# 02_IO_PORTS.net
KiCad netlist of a schematic drawn in Altium Designer
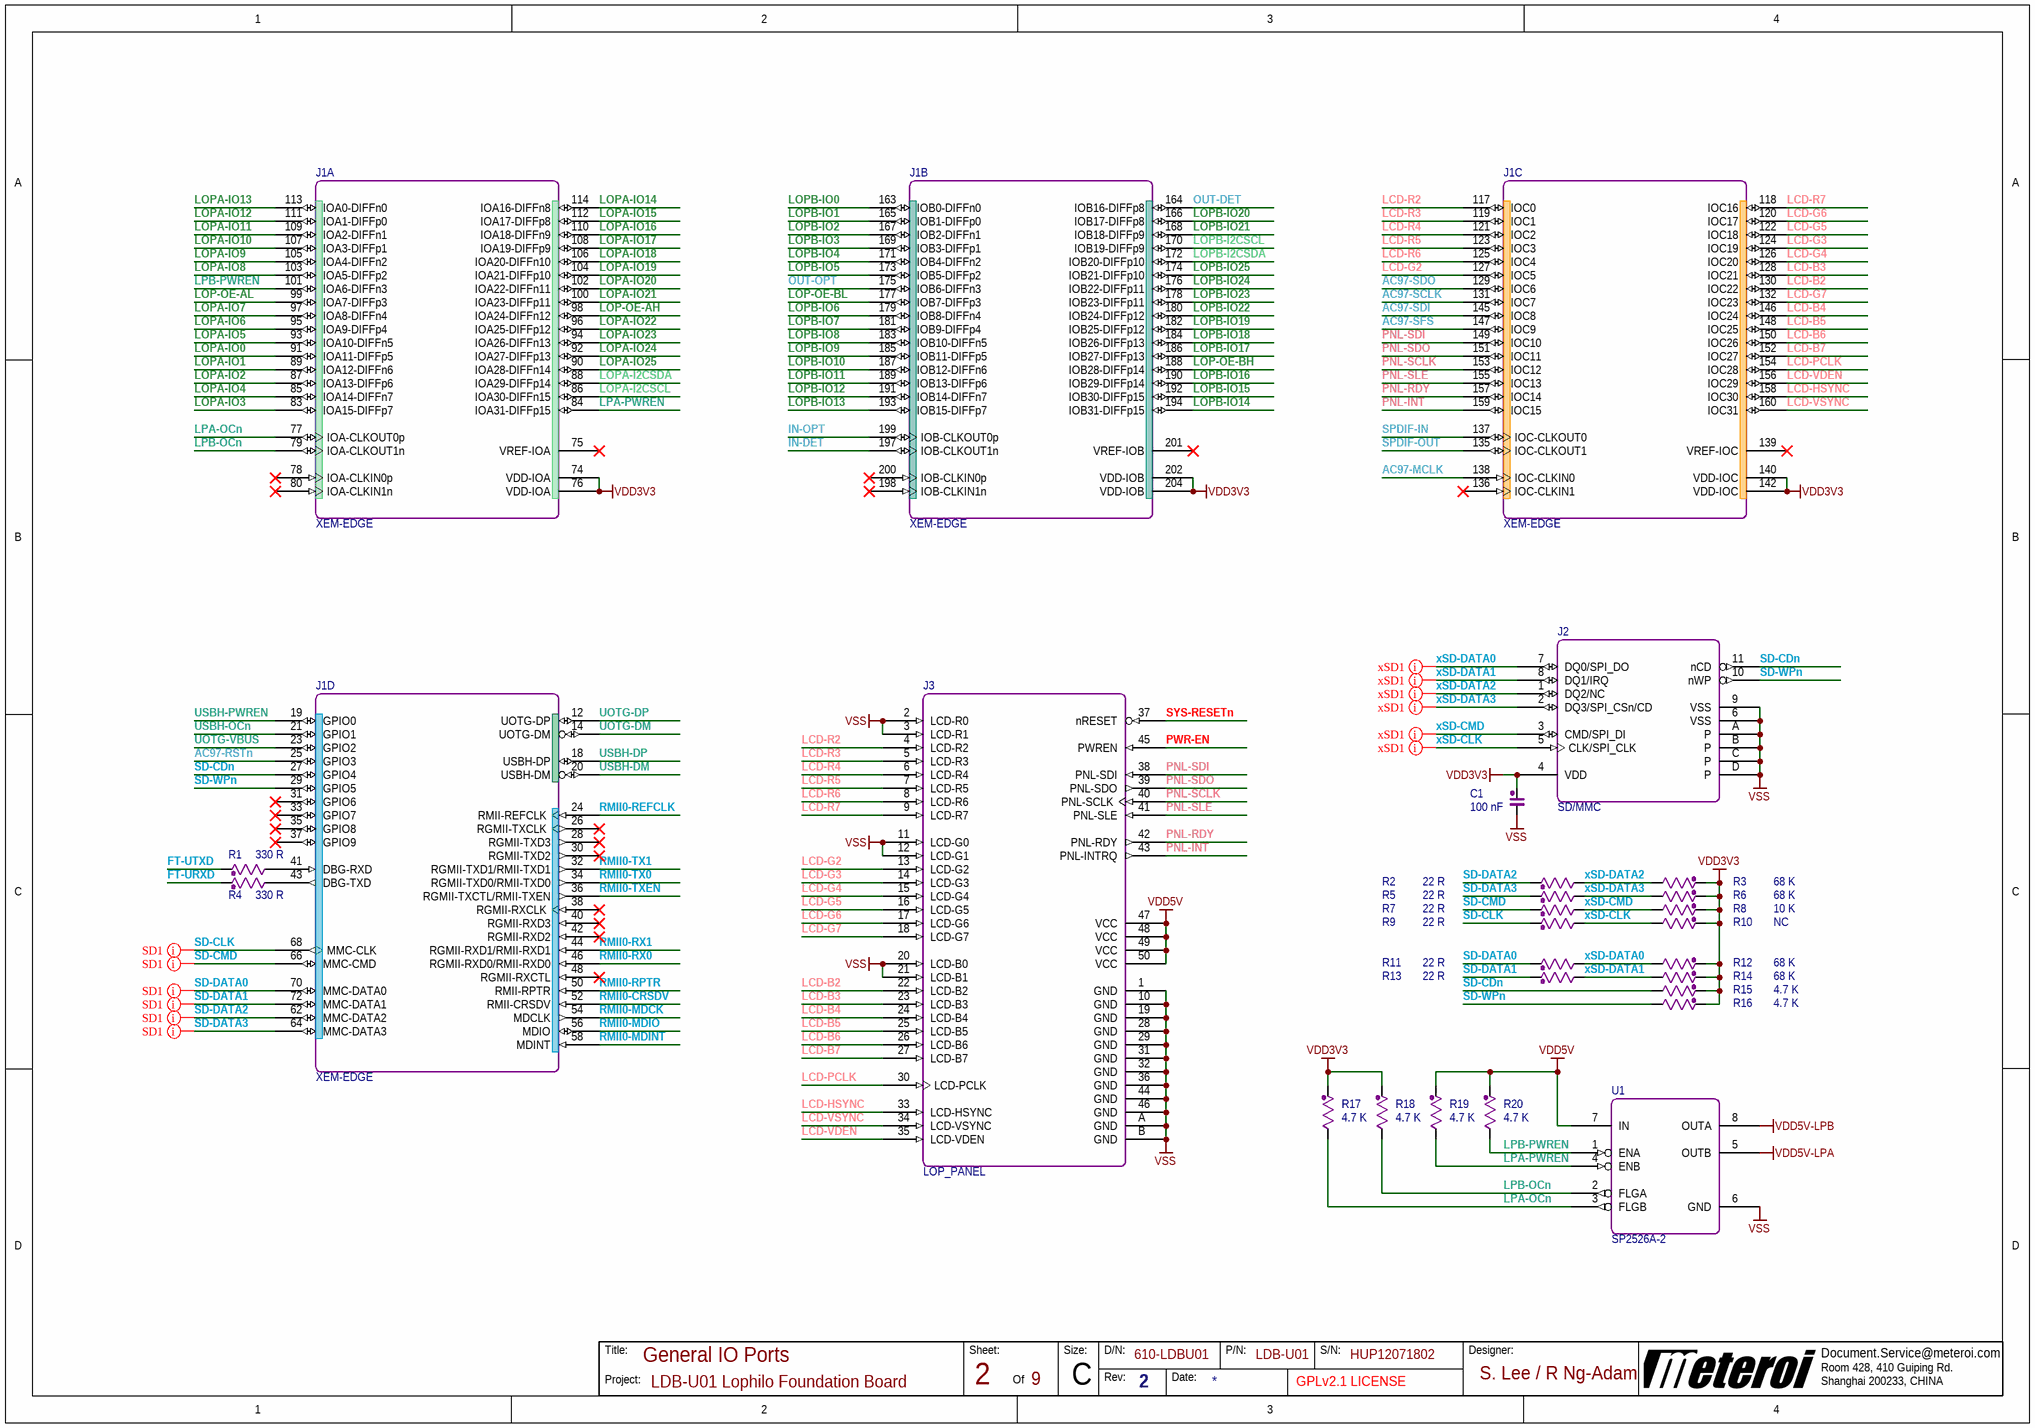
[diagram p0: 02_IO_PORTS.SchDoc]

(export (version "E")
  (design (tool "Eeschema 10.0.6"))
  (components
    (comp (ref "C1")
      (value "100 nF")
      (footprint "0603A1")
      (description "Normal Capacitor")
      (fields
        (field (name "PARTNUMBER") "0")
        (field (name "PUBLISHER") "Cowin")
        (field (name "DESIGNER") "shyul")
      )
      (libsource (lib "Basc_1_Passive") (part "CAP"))
    )
    (comp (ref "J1")
      (value "XEM-EDGE")
      (footprint "XEM-1S-204")
      (description "XEM Edge Connector 204-pins")
      (fields (field (name "PUBLISHER") "Cowin") (field (name "DESIGNER") "shyul"))
      (libsource (lib "PCB_LDB-U01") (part "XEM-SLOT"))
    )
    (comp (ref "J2")
      (value "SD/MMC")
      (footprint "SD_SOCKET_C")
      (description "SD/MMC CARD Socket")
      (fields
        (field (name "PARTNUMBER") "2041021-1")
        (field (name "PUBLISHER") "Cowin")
        (field (name "DESIGNER") "shyul")
      )
      (libsource (lib "Connector_1_General") (part "SD_JACK_2"))
    )
    (comp (ref "J3")
      (value "LOP_PANEL")
      (footprint "FPC_0P5_50A")
      (description "Lophilo Panel Interface")
      (fields (field (name "PUBLISHER") "Cowin") (field (name "DESIGNER") "shyul"))
      (libsource (lib "PCB_LDB-U01") (part "LOP_PANEL"))
    )
    (comp (ref "R1")
      (value "330 R")
      (footprint "0603A2")
      (description "Normal Resistor")
      (fields
        (field (name "PARTNUMBER") "0")
        (field (name "DESIGNER") "shyul")
        (field (name "PUBLISHER") "Cowin")
      )
      (libsource (lib "Basc_1_Passive") (part "RES"))
    )
    (comp (ref "R2")
      (value "22 R")
      (footprint "0402A2")
      (description "Normal Resistor")
      (fields
        (field (name "PARTNUMBER") "0")
        (field (name "DESIGNER") "shyul")
        (field (name "PUBLISHER") "Cowin")
      )
      (libsource (lib "Basc_1_Passive") (part "RES"))
    )
    (comp (ref "R3")
      (value "68 K")
      (footprint "0402A2")
      (description "Normal Resistor")
      (fields
        (field (name "PARTNUMBER") "0")
        (field (name "DESIGNER") "shyul")
        (field (name "PUBLISHER") "Cowin")
      )
      (libsource (lib "Basc_1_Passive") (part "RES"))
    )
    (comp (ref "R4")
      (value "330 R")
      (footprint "0603A2")
      (description "Normal Resistor")
      (fields
        (field (name "PARTNUMBER") "0")
        (field (name "DESIGNER") "shyul")
        (field (name "PUBLISHER") "Cowin")
      )
      (libsource (lib "Basc_1_Passive") (part "RES"))
    )
    (comp (ref "R5")
      (value "22 R")
      (footprint "0402A2")
      (description "Normal Resistor")
      (fields
        (field (name "PARTNUMBER") "0")
        (field (name "DESIGNER") "shyul")
        (field (name "PUBLISHER") "Cowin")
      )
      (libsource (lib "Basc_1_Passive") (part "RES"))
    )
    (comp (ref "R6")
      (value "68 K")
      (footprint "0402A2")
      (description "Normal Resistor")
      (fields
        (field (name "PARTNUMBER") "0")
        (field (name "DESIGNER") "shyul")
        (field (name "PUBLISHER") "Cowin")
      )
      (libsource (lib "Basc_1_Passive") (part "RES"))
    )
    (comp (ref "R7")
      (value "22 R")
      (footprint "0402A2")
      (description "Normal Resistor")
      (fields
        (field (name "PARTNUMBER") "0")
        (field (name "DESIGNER") "shyul")
        (field (name "PUBLISHER") "Cowin")
      )
      (libsource (lib "Basc_1_Passive") (part "RES"))
    )
    (comp (ref "R8")
      (value "10 K")
      (footprint "0402A2")
      (description "Normal Resistor")
      (fields
        (field (name "PARTNUMBER") "0")
        (field (name "DESIGNER") "shyul")
        (field (name "PUBLISHER") "Cowin")
      )
      (libsource (lib "Basc_1_Passive") (part "RES"))
    )
    (comp (ref "R9")
      (value "22 R")
      (footprint "0402A2")
      (description "Normal Resistor")
      (fields
        (field (name "PARTNUMBER") "0")
        (field (name "DESIGNER") "shyul")
        (field (name "PUBLISHER") "Cowin")
      )
      (libsource (lib "Basc_1_Passive") (part "RES"))
    )
    (comp (ref "R10")
      (value "NC")
      (footprint "0402A2")
      (description "Normal Resistor")
      (fields
        (field (name "PARTNUMBER") "0")
        (field (name "DESIGNER") "shyul")
        (field (name "PUBLISHER") "Cowin")
      )
      (libsource (lib "Basc_1_Passive") (part "RES"))
    )
    (comp (ref "R11")
      (value "22 R")
      (footprint "0402A2")
      (description "Normal Resistor")
      (fields
        (field (name "PARTNUMBER") "0")
        (field (name "DESIGNER") "shyul")
        (field (name "PUBLISHER") "Cowin")
      )
      (libsource (lib "Basc_1_Passive") (part "RES"))
    )
    (comp (ref "R12")
      (value "68 K")
      (footprint "0402A2")
      (description "Normal Resistor")
      (fields
        (field (name "PARTNUMBER") "0")
        (field (name "DESIGNER") "shyul")
        (field (name "PUBLISHER") "Cowin")
      )
      (libsource (lib "Basc_1_Passive") (part "RES"))
    )
    (comp (ref "R13")
      (value "22 R")
      (footprint "0402A2")
      (description "Normal Resistor")
      (fields
        (field (name "PARTNUMBER") "0")
        (field (name "DESIGNER") "shyul")
        (field (name "PUBLISHER") "Cowin")
      )
      (libsource (lib "Basc_1_Passive") (part "RES"))
    )
    (comp (ref "R14")
      (value "68 K")
      (footprint "0402A2")
      (description "Normal Resistor")
      (fields
        (field (name "PARTNUMBER") "0")
        (field (name "DESIGNER") "shyul")
        (field (name "PUBLISHER") "Cowin")
      )
      (libsource (lib "Basc_1_Passive") (part "RES"))
    )
    (comp (ref "R15")
      (value "4.7 K")
      (footprint "0603A2")
      (description "Normal Resistor")
      (fields
        (field (name "PARTNUMBER") "0")
        (field (name "DESIGNER") "shyul")
        (field (name "PUBLISHER") "Cowin")
      )
      (libsource (lib "Basc_1_Passive") (part "RES"))
    )
    (comp (ref "R16")
      (value "4.7 K")
      (footprint "0603A2")
      (description "Normal Resistor")
      (fields
        (field (name "PARTNUMBER") "0")
        (field (name "DESIGNER") "shyul")
        (field (name "PUBLISHER") "Cowin")
      )
      (libsource (lib "Basc_1_Passive") (part "RES"))
    )
    (comp (ref "R17")
      (value "4.7 K")
      (footprint "0402A2")
      (description "Normal Resistor")
      (fields
        (field (name "PARTNUMBER") "0")
        (field (name "DESIGNER") "shyul")
        (field (name "PUBLISHER") "Cowin")
      )
      (libsource (lib "Basc_1_Passive") (part "RES"))
    )
    (comp (ref "R18")
      (value "4.7 K")
      (footprint "0402A2")
      (description "Normal Resistor")
      (fields
        (field (name "PARTNUMBER") "0")
        (field (name "DESIGNER") "shyul")
        (field (name "PUBLISHER") "Cowin")
      )
      (libsource (lib "Basc_1_Passive") (part "RES"))
    )
    (comp (ref "R19")
      (value "4.7 K")
      (footprint "0603A2")
      (description "Normal Resistor")
      (fields
        (field (name "PARTNUMBER") "0")
        (field (name "DESIGNER") "shyul")
        (field (name "PUBLISHER") "Cowin")
      )
      (libsource (lib "Basc_1_Passive") (part "RES"))
    )
    (comp (ref "R20")
      (value "4.7 K")
      (footprint "0603A2")
      (description "Normal Resistor")
      (fields
        (field (name "PARTNUMBER") "0")
        (field (name "DESIGNER") "shyul")
        (field (name "PUBLISHER") "Cowin")
      )
      (libsource (lib "Basc_1_Passive") (part "RES"))
    )
    (comp (ref "U1")
      (value "SP2526A-2")
      (footprint "SOIC-8S")
      (description "Power Switch")
      (fields
        (field (name "PARTNUMBER") "SP2526A-2EN")
        (field (name "PUBLISHER") "Cowin")
        (field (name "DESIGNER") "shyul")
      )
      (libsource (lib "PCB_MDB-U01") (part "SP2526A-2"))
    )
  )
  (nets
    (net (code "1") (name "/AC97-MCLK") (class "Default")
      (node (ref "J1") (pin "138") (pinfunction "IOC-CLKIN0_138") (pintype "input"))
    )
    (net (code "2") (name "/AC97-RSTn") (class "Default")
      (node (ref "J1") (pin "25") (pinfunction "GPIO3_25") (pintype "bidirectional"))
    )
    (net (code "3") (name "/AC97-SCLK") (class "Default")
      (node (ref "J1") (pin "131") (pinfunction "IOC7_131") (pintype "bidirectional"))
    )
    (net (code "4") (name "/AC97-SDI") (class "Default")
      (node (ref "J1") (pin "145") (pinfunction "IOC8_145") (pintype "bidirectional"))
    )
    (net (code "5") (name "/AC97-SDO") (class "Default")
      (node (ref "J1") (pin "129") (pinfunction "IOC6_129") (pintype "bidirectional"))
    )
    (net (code "6") (name "/AC97-SFS") (class "Default")
      (node (ref "J1") (pin "147") (pinfunction "IOC9_147") (pintype "bidirectional"))
    )
    (net (code "7") (name "/FT-URXD") (class "Default")
      (node (ref "R4") (pin "2") (pinfunction "2_2") (pintype "passive"))
    )
    (net (code "8") (name "/FT-UTXD") (class "Default")
      (node (ref "R1") (pin "2") (pinfunction "2_2") (pintype "passive"))
    )
    (net (code "9") (name "/IN-DET") (class "Default")
      (node (ref "J1") (pin "197") (pinfunction "IOB-CLKOUT1n_197") (pintype "bidirectional"))
    )
    (net (code "10") (name "/IN-OPT") (class "Default")
      (node (ref "J1") (pin "199") (pinfunction "IOB-CLKOUT0p_199") (pintype "bidirectional"))
    )
    (net (code "11") (name "/LCD-B2") (class "Default")
      (node (ref "J1") (pin "130") (pinfunction "IOC22_130") (pintype "bidirectional"))
      (node (ref "J3") (pin "22") (pinfunction "LCD-B2_22") (pintype "input"))
    )
    (net (code "12") (name "/LCD-B3") (class "Default")
      (node (ref "J1") (pin "128") (pinfunction "IOC21_128") (pintype "bidirectional"))
      (node (ref "J3") (pin "23") (pinfunction "LCD-B3_23") (pintype "input"))
    )
    (net (code "13") (name "/LCD-B4") (class "Default")
      (node (ref "J1") (pin "146") (pinfunction "IOC24_146") (pintype "bidirectional"))
      (node (ref "J3") (pin "24") (pinfunction "LCD-B4_24") (pintype "input"))
    )
    (net (code "14") (name "/LCD-B5") (class "Default")
      (node (ref "J1") (pin "148") (pinfunction "IOC25_148") (pintype "bidirectional"))
      (node (ref "J3") (pin "25") (pinfunction "LCD-B5_25") (pintype "input"))
    )
    (net (code "15") (name "/LCD-B6") (class "Default")
      (node (ref "J1") (pin "150") (pinfunction "IOC26_150") (pintype "bidirectional"))
      (node (ref "J3") (pin "26") (pinfunction "LCD-B6_26") (pintype "input"))
    )
    (net (code "16") (name "/LCD-B7") (class "Default")
      (node (ref "J1") (pin "152") (pinfunction "IOC27_152") (pintype "bidirectional"))
      (node (ref "J3") (pin "27") (pinfunction "LCD-B7_27") (pintype "input"))
    )
    (net (code "17") (name "/LCD-G2") (class "Default")
      (node (ref "J1") (pin "127") (pinfunction "IOC5_127") (pintype "bidirectional"))
      (node (ref "J3") (pin "13") (pinfunction "LCD-G2_13") (pintype "input"))
    )
    (net (code "18") (name "/LCD-G3") (class "Default")
      (node (ref "J1") (pin "124") (pinfunction "IOC19_124") (pintype "bidirectional"))
      (node (ref "J3") (pin "14") (pinfunction "LCD-G3_14") (pintype "input"))
    )
    (net (code "19") (name "/LCD-G4") (class "Default")
      (node (ref "J1") (pin "126") (pinfunction "IOC20_126") (pintype "bidirectional"))
      (node (ref "J3") (pin "15") (pinfunction "LCD-G4_15") (pintype "input"))
    )
    (net (code "20") (name "/LCD-G5") (class "Default")
      (node (ref "J1") (pin "122") (pinfunction "IOC18_122") (pintype "bidirectional"))
      (node (ref "J3") (pin "16") (pinfunction "LCD-G5_16") (pintype "input"))
    )
    (net (code "21") (name "/LCD-G6") (class "Default")
      (node (ref "J1") (pin "120") (pinfunction "IOC17_120") (pintype "bidirectional"))
      (node (ref "J3") (pin "17") (pinfunction "LCD-G6_17") (pintype "input"))
    )
    (net (code "22") (name "/LCD-G7") (class "Default")
      (node (ref "J1") (pin "132") (pinfunction "IOC23_132") (pintype "bidirectional"))
      (node (ref "J3") (pin "18") (pinfunction "LCD-G7_18") (pintype "input"))
    )
    (net (code "23") (name "/LCD-HSYNC") (class "Default")
      (node (ref "J1") (pin "158") (pinfunction "IOC30_158") (pintype "bidirectional"))
      (node (ref "J3") (pin "33") (pinfunction "LCD-HSYNC_33") (pintype "input"))
    )
    (net (code "24") (name "/LCD-PCLK") (class "Default")
      (node (ref "J1") (pin "154") (pinfunction "IOC28_154") (pintype "bidirectional"))
      (node (ref "J3") (pin "30") (pinfunction "LCD-PCLK_30") (pintype "input"))
    )
    (net (code "25") (name "/LCD-R2") (class "Default")
      (node (ref "J1") (pin "117") (pinfunction "IOC0_117") (pintype "bidirectional"))
      (node (ref "J3") (pin "4") (pinfunction "LCD-R2_4") (pintype "input"))
    )
    (net (code "26") (name "/LCD-R3") (class "Default")
      (node (ref "J1") (pin "119") (pinfunction "IOC1_119") (pintype "bidirectional"))
      (node (ref "J3") (pin "5") (pinfunction "LCD-R3_5") (pintype "input"))
    )
    (net (code "27") (name "/LCD-R4") (class "Default")
      (node (ref "J1") (pin "121") (pinfunction "IOC2_121") (pintype "bidirectional"))
      (node (ref "J3") (pin "6") (pinfunction "LCD-R4_6") (pintype "input"))
    )
    (net (code "28") (name "/LCD-R5") (class "Default")
      (node (ref "J1") (pin "123") (pinfunction "IOC3_123") (pintype "bidirectional"))
      (node (ref "J3") (pin "7") (pinfunction "LCD-R5_7") (pintype "input"))
    )
    (net (code "29") (name "/LCD-R6") (class "Default")
      (node (ref "J1") (pin "125") (pinfunction "IOC4_125") (pintype "bidirectional"))
      (node (ref "J3") (pin "8") (pinfunction "LCD-R6_8") (pintype "input"))
    )
    (net (code "30") (name "/LCD-R7") (class "Default")
      (node (ref "J1") (pin "118") (pinfunction "IOC16_118") (pintype "bidirectional"))
      (node (ref "J3") (pin "9") (pinfunction "LCD-R7_9") (pintype "input"))
    )
    (net (code "31") (name "/LCD-VDEN") (class "Default")
      (node (ref "J1") (pin "156") (pinfunction "IOC29_156") (pintype "bidirectional"))
      (node (ref "J3") (pin "35") (pinfunction "LCD-VDEN_35") (pintype "input"))
    )
    (net (code "32") (name "/LCD-VSYNC") (class "Default")
      (node (ref "J1") (pin "160") (pinfunction "IOC31_160") (pintype "bidirectional"))
      (node (ref "J3") (pin "34") (pinfunction "LCD-VSYNC_34") (pintype "input"))
    )
    (net (code "33") (name "/LOP-OE-AH") (class "Default")
      (node (ref "J1") (pin "98") (pinfunction "IOA24-DIFFn12_98") (pintype "bidirectional"))
    )
    (net (code "34") (name "/LOP-OE-AL") (class "Default")
      (node (ref "J1") (pin "99") (pinfunction "IOA7-DIFFp3_99") (pintype "bidirectional"))
    )
    (net (code "35") (name "/LOP-OE-BH") (class "Default")
      (node (ref "J1") (pin "188") (pinfunction "IOB28-DIFFp14_188") (pintype "bidirectional"))
    )
    (net (code "36") (name "/LOP-OE-BL") (class "Default")
      (node (ref "J1") (pin "177") (pinfunction "IOB7-DIFFp3_177") (pintype "bidirectional"))
    )
    (net (code "37") (name "/LOPA-I2CSCL") (class "Default")
      (node (ref "J1") (pin "86") (pinfunction "IOA30-DIFFn15_86") (pintype "bidirectional"))
    )
    (net (code "38") (name "/LOPA-I2CSDA") (class "Default")
      (node (ref "J1") (pin "88") (pinfunction "IOA29-DIFFp14_88") (pintype "bidirectional"))
    )
    (net (code "39") (name "/LOPA-IO0") (class "Default")
      (node (ref "J1") (pin "91") (pinfunction "IOA11-DIFFp5_91") (pintype "bidirectional"))
    )
    (net (code "40") (name "/LOPA-IO1") (class "Default")
      (node (ref "J1") (pin "89") (pinfunction "IOA12-DIFFn6_89") (pintype "bidirectional"))
    )
    (net (code "41") (name "/LOPA-IO2") (class "Default")
      (node (ref "J1") (pin "87") (pinfunction "IOA13-DIFFp6_87") (pintype "bidirectional"))
    )
    (net (code "42") (name "/LOPA-IO3") (class "Default")
      (node (ref "J1") (pin "83") (pinfunction "IOA15-DIFFp7_83") (pintype "bidirectional"))
    )
    (net (code "43") (name "/LOPA-IO4") (class "Default")
      (node (ref "J1") (pin "85") (pinfunction "IOA14-DIFFn7_85") (pintype "bidirectional"))
    )
    (net (code "44") (name "/LOPA-IO5") (class "Default")
      (node (ref "J1") (pin "93") (pinfunction "IOA10-DIFFn5_93") (pintype "bidirectional"))
    )
    (net (code "45") (name "/LOPA-IO6") (class "Default")
      (node (ref "J1") (pin "95") (pinfunction "IOA9-DIFFp4_95") (pintype "bidirectional"))
    )
    (net (code "46") (name "/LOPA-IO7") (class "Default")
      (node (ref "J1") (pin "97") (pinfunction "IOA8-DIFFn4_97") (pintype "bidirectional"))
    )
    (net (code "47") (name "/LOPA-IO8") (class "Default")
      (node (ref "J1") (pin "103") (pinfunction "IOA5-DIFFp2_103") (pintype "bidirectional"))
    )
    (net (code "48") (name "/LOPA-IO9") (class "Default")
      (node (ref "J1") (pin "105") (pinfunction "IOA4-DIFFn2_105") (pintype "bidirectional"))
    )
    (net (code "49") (name "/LOPA-IO10") (class "Default")
      (node (ref "J1") (pin "107") (pinfunction "IOA3-DIFFp1_107") (pintype "bidirectional"))
    )
    (net (code "50") (name "/LOPA-IO11") (class "Default")
      (node (ref "J1") (pin "109") (pinfunction "IOA2-DIFFn1_109") (pintype "bidirectional"))
    )
    (net (code "51") (name "/LOPA-IO12") (class "Default")
      (node (ref "J1") (pin "111") (pinfunction "IOA1-DIFFp0_111") (pintype "bidirectional"))
    )
    (net (code "52") (name "/LOPA-IO13") (class "Default")
      (node (ref "J1") (pin "113") (pinfunction "IOA0-DIFFn0_113") (pintype "bidirectional"))
    )
    (net (code "53") (name "/LOPA-IO14") (class "Default")
      (node (ref "J1") (pin "114") (pinfunction "IOA16-DIFFn8_114") (pintype "bidirectional"))
    )
    (net (code "54") (name "/LOPA-IO15") (class "Default")
      (node (ref "J1") (pin "112") (pinfunction "IOA17-DIFFp8_112") (pintype "bidirectional"))
    )
    (net (code "55") (name "/LOPA-IO16") (class "Default")
      (node (ref "J1") (pin "110") (pinfunction "IOA18-DIFFn9_110") (pintype "bidirectional"))
    )
    (net (code "56") (name "/LOPA-IO17") (class "Default")
      (node (ref "J1") (pin "108") (pinfunction "IOA19-DIFFp9_108") (pintype "bidirectional"))
    )
    (net (code "57") (name "/LOPA-IO18") (class "Default")
      (node (ref "J1") (pin "106") (pinfunction "IOA20-DIFFn10_106") (pintype "bidirectional"))
    )
    (net (code "58") (name "/LOPA-IO19") (class "Default")
      (node (ref "J1") (pin "104") (pinfunction "IOA21-DIFFp10_104") (pintype "bidirectional"))
    )
    (net (code "59") (name "/LOPA-IO20") (class "Default")
      (node (ref "J1") (pin "102") (pinfunction "IOA22-DIFFn11_102") (pintype "bidirectional"))
    )
    (net (code "60") (name "/LOPA-IO21") (class "Default")
      (node (ref "J1") (pin "100") (pinfunction "IOA23-DIFFp11_100") (pintype "bidirectional"))
    )
    (net (code "61") (name "/LOPA-IO22") (class "Default")
      (node (ref "J1") (pin "96") (pinfunction "IOA25-DIFFp12_96") (pintype "bidirectional"))
    )
    (net (code "62") (name "/LOPA-IO23") (class "Default")
      (node (ref "J1") (pin "94") (pinfunction "IOA26-DIFFn13_94") (pintype "bidirectional"))
    )
    (net (code "63") (name "/LOPA-IO24") (class "Default")
      (node (ref "J1") (pin "92") (pinfunction "IOA27-DIFFp13_92") (pintype "bidirectional"))
    )
    (net (code "64") (name "/LOPA-IO25") (class "Default")
      (node (ref "J1") (pin "90") (pinfunction "IOA28-DIFFn14_90") (pintype "bidirectional"))
    )
    (net (code "65") (name "/LOPB-I2CSCL") (class "Default")
      (node (ref "J1") (pin "170") (pinfunction "IOB19-DIFFp9_170") (pintype "bidirectional"))
    )
    (net (code "66") (name "/LOPB-I2CSDA") (class "Default")
      (node (ref "J1") (pin "172") (pinfunction "IOB20-DIFFp10_172") (pintype "bidirectional"))
    )
    (net (code "67") (name "/LOPB-IO0") (class "Default")
      (node (ref "J1") (pin "163") (pinfunction "IOB0-DIFFn0_163") (pintype "bidirectional"))
    )
    (net (code "68") (name "/LOPB-IO1") (class "Default")
      (node (ref "J1") (pin "165") (pinfunction "IOB1-DIFFp0_165") (pintype "bidirectional"))
    )
    (net (code "69") (name "/LOPB-IO2") (class "Default")
      (node (ref "J1") (pin "167") (pinfunction "IOB2-DIFFn1_167") (pintype "bidirectional"))
    )
    (net (code "70") (name "/LOPB-IO3") (class "Default")
      (node (ref "J1") (pin "169") (pinfunction "IOB3-DIFFp1_169") (pintype "bidirectional"))
    )
    (net (code "71") (name "/LOPB-IO4") (class "Default")
      (node (ref "J1") (pin "171") (pinfunction "IOB4-DIFFn2_171") (pintype "bidirectional"))
    )
    (net (code "72") (name "/LOPB-IO5") (class "Default")
      (node (ref "J1") (pin "173") (pinfunction "IOB5-DIFFp2_173") (pintype "bidirectional"))
    )
    (net (code "73") (name "/LOPB-IO6") (class "Default")
      (node (ref "J1") (pin "179") (pinfunction "IOB8-DIFFn4_179") (pintype "bidirectional"))
    )
    (net (code "74") (name "/LOPB-IO7") (class "Default")
      (node (ref "J1") (pin "181") (pinfunction "IOB9-DIFFp4_181") (pintype "bidirectional"))
    )
    (net (code "75") (name "/LOPB-IO8") (class "Default")
      (node (ref "J1") (pin "183") (pinfunction "IOB10-DIFFn5_183") (pintype "bidirectional"))
    )
    (net (code "76") (name "/LOPB-IO9") (class "Default")
      (node (ref "J1") (pin "185") (pinfunction "IOB11-DIFFp5_185") (pintype "bidirectional"))
    )
    (net (code "77") (name "/LOPB-IO10") (class "Default")
      (node (ref "J1") (pin "187") (pinfunction "IOB12-DIFFn6_187") (pintype "bidirectional"))
    )
    (net (code "78") (name "/LOPB-IO11") (class "Default")
      (node (ref "J1") (pin "189") (pinfunction "IOB13-DIFFp6_189") (pintype "bidirectional"))
    )
    (net (code "79") (name "/LOPB-IO12") (class "Default")
      (node (ref "J1") (pin "191") (pinfunction "IOB14-DIFFn7_191") (pintype "bidirectional"))
    )
    (net (code "80") (name "/LOPB-IO13") (class "Default")
      (node (ref "J1") (pin "193") (pinfunction "IOB15-DIFFp7_193") (pintype "bidirectional"))
    )
    (net (code "81") (name "/LOPB-IO14") (class "Default")
      (node (ref "J1") (pin "194") (pinfunction "IOB31-DIFFp15_194") (pintype "bidirectional"))
    )
    (net (code "82") (name "/LOPB-IO15") (class "Default")
      (node (ref "J1") (pin "192") (pinfunction "IOB30-DIFFp15_192") (pintype "bidirectional"))
    )
    (net (code "83") (name "/LOPB-IO16") (class "Default")
      (node (ref "J1") (pin "190") (pinfunction "IOB29-DIFFp14_190") (pintype "bidirectional"))
    )
    (net (code "84") (name "/LOPB-IO17") (class "Default")
      (node (ref "J1") (pin "186") (pinfunction "IOB27-DIFFp13_186") (pintype "bidirectional"))
    )
    (net (code "85") (name "/LOPB-IO18") (class "Default")
      (node (ref "J1") (pin "184") (pinfunction "IOB26-DIFFp13_184") (pintype "bidirectional"))
    )
    (net (code "86") (name "/LOPB-IO19") (class "Default")
      (node (ref "J1") (pin "182") (pinfunction "IOB25-DIFFp12_182") (pintype "bidirectional"))
    )
    (net (code "87") (name "/LOPB-IO20") (class "Default")
      (node (ref "J1") (pin "166") (pinfunction "IOB17-DIFFp8_166") (pintype "bidirectional"))
    )
    (net (code "88") (name "/LOPB-IO21") (class "Default")
      (node (ref "J1") (pin "168") (pinfunction "IOB18-DIFFp9_168") (pintype "bidirectional"))
    )
    (net (code "89") (name "/LOPB-IO22") (class "Default")
      (node (ref "J1") (pin "180") (pinfunction "IOB24-DIFFp12_180") (pintype "bidirectional"))
    )
    (net (code "90") (name "/LOPB-IO23") (class "Default")
      (node (ref "J1") (pin "178") (pinfunction "IOB23-DIFFp11_178") (pintype "bidirectional"))
    )
    (net (code "91") (name "/LOPB-IO24") (class "Default")
      (node (ref "J1") (pin "176") (pinfunction "IOB22-DIFFp11_176") (pintype "bidirectional"))
    )
    (net (code "92") (name "/LOPB-IO25") (class "Default")
      (node (ref "J1") (pin "174") (pinfunction "IOB21-DIFFp10_174") (pintype "bidirectional"))
    )
    (net (code "93") (name "/LPA-OCn") (class "Default")
      (node (ref "J1") (pin "77") (pinfunction "IOA-CLKOUT0p_77") (pintype "bidirectional"))
      (node (ref "R17") (pin "1") (pinfunction "1_1") (pintype "passive"))
      (node (ref "U1") (pin "3") (pinfunction "FLGB_3") (pintype "output"))
    )
    (net (code "94") (name "/LPA-PWREN") (class "Default")
      (node (ref "J1") (pin "84") (pinfunction "IOA31-DIFFp15_84") (pintype "bidirectional"))
      (node (ref "R19") (pin "1") (pinfunction "1_1") (pintype "passive"))
      (node (ref "U1") (pin "4") (pinfunction "ENB_4") (pintype "input"))
    )
    (net (code "95") (name "/LPB-OCn") (class "Default")
      (node (ref "J1") (pin "79") (pinfunction "IOA-CLKOUT1n_79") (pintype "bidirectional"))
      (node (ref "R18") (pin "1") (pinfunction "1_1") (pintype "passive"))
      (node (ref "U1") (pin "2") (pinfunction "FLGA_2") (pintype "output"))
    )
    (net (code "96") (name "/LPB-PWREN") (class "Default")
      (node (ref "J1") (pin "101") (pinfunction "IOA6-DIFFn3_101") (pintype "bidirectional"))
      (node (ref "R20") (pin "1") (pinfunction "1_1") (pintype "passive"))
      (node (ref "U1") (pin "1") (pinfunction "ENA_1") (pintype "input"))
    )
    (net (code "97") (name "/OUT-DET") (class "Default")
      (node (ref "J1") (pin "164") (pinfunction "IOB16-DIFFp8_164") (pintype "bidirectional"))
    )
    (net (code "98") (name "/OUT-OPT") (class "Default")
      (node (ref "J1") (pin "175") (pinfunction "IOB6-DIFFn3_175") (pintype "bidirectional"))
    )
    (net (code "99") (name "/PNL-INT") (class "Default")
      (node (ref "J1") (pin "159") (pinfunction "IOC15_159") (pintype "bidirectional"))
      (node (ref "J3") (pin "43") (pinfunction "PNL-INTRQ_43") (pintype "output"))
    )
    (net (code "100") (name "/PNL-RDY") (class "Default")
      (node (ref "J1") (pin "157") (pinfunction "IOC14_157") (pintype "bidirectional"))
      (node (ref "J3") (pin "42") (pinfunction "PNL-RDY_42") (pintype "output"))
    )
    (net (code "101") (name "/PNL-SCLK") (class "Default")
      (node (ref "J1") (pin "153") (pinfunction "IOC12_153") (pintype "bidirectional"))
      (node (ref "J3") (pin "40") (pinfunction "PNL-SCLK_40") (pintype "input"))
    )
    (net (code "102") (name "/PNL-SDI") (class "Default")
      (node (ref "J1") (pin "149") (pinfunction "IOC10_149") (pintype "bidirectional"))
      (node (ref "J3") (pin "38") (pinfunction "PNL-SDI_38") (pintype "input"))
    )
    (net (code "103") (name "/PNL-SDO") (class "Default")
      (node (ref "J1") (pin "151") (pinfunction "IOC11_151") (pintype "bidirectional"))
      (node (ref "J3") (pin "39") (pinfunction "PNL-SDO_39") (pintype "output"))
    )
    (net (code "104") (name "/PNL-SLE") (class "Default")
      (node (ref "J1") (pin "155") (pinfunction "IOC13_155") (pintype "bidirectional"))
      (node (ref "J3") (pin "41") (pinfunction "PNL-SLE_41") (pintype "input"))
    )
    (net (code "105") (name "/PWR-EN") (class "Default")
      (node (ref "J3") (pin "45") (pinfunction "PWREN_45") (pintype "input"))
    )
    (net (code "106") (name "/RMII0-CRSDV") (class "Default")
      (node (ref "J1") (pin "52") (pinfunction "RMII-CRSDV_52") (pintype "input"))
    )
    (net (code "107") (name "/RMII0-MDCK") (class "Default")
      (node (ref "J1") (pin "54") (pinfunction "MDCLK_54") (pintype "output"))
    )
    (net (code "108") (name "/RMII0-MDINT") (class "Default")
      (node (ref "J1") (pin "58") (pinfunction "MDINT_58") (pintype "input"))
    )
    (net (code "109") (name "/RMII0-MDIO") (class "Default")
      (node (ref "J1") (pin "56") (pinfunction "MDIO_56") (pintype "bidirectional"))
    )
    (net (code "110") (name "/RMII0-REFCLK") (class "Default")
      (node (ref "J1") (pin "24") (pinfunction "RMII-REFCLK_24") (pintype "input"))
    )
    (net (code "111") (name "/RMII0-RPTR") (class "Default")
      (node (ref "J1") (pin "50") (pinfunction "RMII-RPTR_50") (pintype "input"))
    )
    (net (code "112") (name "/RMII0-RX0") (class "Default")
      (node (ref "J1") (pin "46") (pinfunction "RGMII-RXD0/RMII-RXD0_46") (pintype "input"))
    )
    (net (code "113") (name "/RMII0-RX1") (class "Default")
      (node (ref "J1") (pin "44") (pinfunction "RGMII-RXD1/RMII-RXD1_44") (pintype "input"))
    )
    (net (code "114") (name "/RMII0-TX0") (class "Default")
      (node (ref "J1") (pin "34") (pinfunction "RGMII-TXD0/RMII-TXD0_34") (pintype "output"))
    )
    (net (code "115") (name "/RMII0-TX1") (class "Default")
      (node (ref "J1") (pin "32") (pinfunction "RGMII-TXD1/RMII-TXD1_32") (pintype "output"))
    )
    (net (code "116") (name "/RMII0-TXEN") (class "Default")
      (node (ref "J1") (pin "36") (pinfunction "RGMII-TXCTL/RMII-TXEN_36") (pintype "output"))
    )
    (net (code "117") (name "/SD-CDn") (class "Default")
      (node (ref "J1") (pin "27") (pinfunction "GPIO4_27") (pintype "bidirectional"))
      (node (ref "J2") (pin "11") (pinfunction "nCD_11") (pintype "output"))
      (node (ref "R15") (pin "1") (pinfunction "1_1") (pintype "passive"))
    )
    (net (code "118") (name "/SD-CLK") (class "Default")
      (node (ref "J1") (pin "68") (pinfunction "MMC-CLK_68") (pintype "output"))
      (node (ref "R9") (pin "2") (pinfunction "2_2") (pintype "passive"))
    )
    (net (code "119") (name "/SD-CMD") (class "Default")
      (node (ref "J1") (pin "66") (pinfunction "MMC-CMD_66") (pintype "bidirectional"))
      (node (ref "R7") (pin "2") (pinfunction "2_2") (pintype "passive"))
    )
    (net (code "120") (name "/SD-DATA0") (class "Default")
      (node (ref "J1") (pin "70") (pinfunction "MMC-DATA0_70") (pintype "bidirectional"))
      (node (ref "R11") (pin "2") (pinfunction "2_2") (pintype "passive"))
    )
    (net (code "121") (name "/SD-DATA1") (class "Default")
      (node (ref "J1") (pin "72") (pinfunction "MMC-DATA1_72") (pintype "bidirectional"))
      (node (ref "R13") (pin "2") (pinfunction "2_2") (pintype "passive"))
    )
    (net (code "122") (name "/SD-DATA2") (class "Default")
      (node (ref "J1") (pin "62") (pinfunction "MMC-DATA2_62") (pintype "bidirectional"))
      (node (ref "R2") (pin "2") (pinfunction "2_2") (pintype "passive"))
    )
    (net (code "123") (name "/SD-DATA3") (class "Default")
      (node (ref "J1") (pin "64") (pinfunction "MMC-DATA3_64") (pintype "bidirectional"))
      (node (ref "R5") (pin "2") (pinfunction "2_2") (pintype "passive"))
    )
    (net (code "124") (name "/SD-WPn") (class "Default")
      (node (ref "J1") (pin "29") (pinfunction "GPIO5_29") (pintype "bidirectional"))
      (node (ref "J2") (pin "10") (pinfunction "nWP_10") (pintype "output"))
      (node (ref "R16") (pin "1") (pinfunction "1_1") (pintype "passive"))
    )
    (net (code "125") (name "/SPDIF-IN") (class "Default")
      (node (ref "J1") (pin "137") (pinfunction "IOC-CLKOUT0_137") (pintype "bidirectional"))
    )
    (net (code "126") (name "/SPDIF-OUT") (class "Default")
      (node (ref "J1") (pin "135") (pinfunction "IOC-CLKOUT1_135") (pintype "bidirectional"))
    )
    (net (code "127") (name "/SYS-RESETn") (class "Default")
      (node (ref "J3") (pin "37") (pinfunction "nRESET_37") (pintype "input"))
    )
    (net (code "128") (name "/UOTG-DM") (class "Default")
      (node (ref "J1") (pin "14") (pinfunction "UOTG-DM_14") (pintype "bidirectional"))
    )
    (net (code "129") (name "/UOTG-DP") (class "Default")
      (node (ref "J1") (pin "12") (pinfunction "UOTG-DP_12") (pintype "bidirectional"))
    )
    (net (code "130") (name "/UOTG-VBUS") (class "Default")
      (node (ref "J1") (pin "23") (pinfunction "GPIO2_23") (pintype "bidirectional"))
    )
    (net (code "131") (name "/USBH-DM") (class "Default")
      (node (ref "J1") (pin "20") (pinfunction "USBH-DM_20") (pintype "bidirectional"))
    )
    (net (code "132") (name "/USBH-DP") (class "Default")
      (node (ref "J1") (pin "18") (pinfunction "USBH-DP_18") (pintype "bidirectional"))
    )
    (net (code "133") (name "/USBH-OCn") (class "Default")
      (node (ref "J1") (pin "21") (pinfunction "GPIO1_21") (pintype "bidirectional"))
    )
    (net (code "134") (name "/USBH-PWREN") (class "Default")
      (node (ref "J1") (pin "19") (pinfunction "GPIO0_19") (pintype "bidirectional"))
    )
    (net (code "135") (name "/xSD-CLK") (class "Default")
      (node (ref "J2") (pin "5") (pinfunction "CLK/SPI_CLK_5") (pintype "input"))
      (node (ref "R10") (pin "1") (pinfunction "1_1") (pintype "passive"))
      (node (ref "R9") (pin "1") (pinfunction "1_1") (pintype "passive"))
    )
    (net (code "136") (name "/xSD-CMD") (class "Default")
      (node (ref "J2") (pin "3") (pinfunction "CMD/SPI_DI_3") (pintype "bidirectional"))
      (node (ref "R7") (pin "1") (pinfunction "1_1") (pintype "passive"))
      (node (ref "R8") (pin "1") (pinfunction "1_1") (pintype "passive"))
    )
    (net (code "137") (name "/xSD-DATA0") (class "Default")
      (node (ref "J2") (pin "7") (pinfunction "DQ0/SPI_DO_7") (pintype "bidirectional"))
      (node (ref "R11") (pin "1") (pinfunction "1_1") (pintype "passive"))
      (node (ref "R12") (pin "1") (pinfunction "1_1") (pintype "passive"))
    )
    (net (code "138") (name "/xSD-DATA1") (class "Default")
      (node (ref "J2") (pin "8") (pinfunction "DQ1/IRQ_8") (pintype "bidirectional"))
      (node (ref "R13") (pin "1") (pinfunction "1_1") (pintype "passive"))
      (node (ref "R14") (pin "1") (pinfunction "1_1") (pintype "passive"))
    )
    (net (code "139") (name "/xSD-DATA2") (class "Default")
      (node (ref "J2") (pin "1") (pinfunction "DQ2/NC_1") (pintype "bidirectional"))
      (node (ref "R2") (pin "1") (pinfunction "1_1") (pintype "passive"))
      (node (ref "R3") (pin "1") (pinfunction "1_1") (pintype "passive"))
    )
    (net (code "140") (name "/xSD-DATA3") (class "Default")
      (node (ref "J2") (pin "2") (pinfunction "DQ3/SPI_CSn/CD_2") (pintype "bidirectional"))
      (node (ref "R5") (pin "1") (pinfunction "1_1") (pintype "passive"))
      (node (ref "R6") (pin "1") (pinfunction "1_1") (pintype "passive"))
    )
    (net (code "141") (name "Net-(J1D-DBG-RXD)") (class "Default")
      (node (ref "J1") (pin "41") (pinfunction "DBG-RXD_41") (pintype "input"))
      (node (ref "R1") (pin "1") (pinfunction "1_1") (pintype "passive"))
    )
    (net (code "142") (name "Net-(J1D-DBG-TXD)") (class "Default")
      (node (ref "J1") (pin "43") (pinfunction "DBG-TXD_43") (pintype "output"))
      (node (ref "R4") (pin "1") (pinfunction "1_1") (pintype "passive"))
    )
    (net (code "143") (name "VDD3V3") (class "Default")
      (node (ref "C1") (pin "2") (pinfunction "2_2") (pintype "passive"))
      (node (ref "J1") (pin "140") (pinfunction "VDD-IOC_140") (pintype "passive"))
      (node (ref "J1") (pin "142") (pinfunction "VDD-IOC_142") (pintype "passive"))
      (node (ref "J1") (pin "202") (pinfunction "VDD-IOB_202") (pintype "passive"))
      (node (ref "J1") (pin "204") (pinfunction "VDD-IOB_204") (pintype "passive"))
      (node (ref "J1") (pin "74") (pinfunction "VDD-IOA_74") (pintype "passive"))
      (node (ref "J1") (pin "76") (pinfunction "VDD-IOA_76") (pintype "passive"))
      (node (ref "J2") (pin "4") (pinfunction "VDD_4") (pintype "power_in"))
      (node (ref "R10") (pin "2") (pinfunction "2_2") (pintype "passive"))
      (node (ref "R12") (pin "2") (pinfunction "2_2") (pintype "passive"))
      (node (ref "R14") (pin "2") (pinfunction "2_2") (pintype "passive"))
      (node (ref "R15") (pin "2") (pinfunction "2_2") (pintype "passive"))
      (node (ref "R16") (pin "2") (pinfunction "2_2") (pintype "passive"))
      (node (ref "R17") (pin "2") (pinfunction "2_2") (pintype "passive"))
      (node (ref "R18") (pin "2") (pinfunction "2_2") (pintype "passive"))
      (node (ref "R3") (pin "2") (pinfunction "2_2") (pintype "passive"))
      (node (ref "R6") (pin "2") (pinfunction "2_2") (pintype "passive"))
      (node (ref "R8") (pin "2") (pinfunction "2_2") (pintype "passive"))
    )
    (net (code "144") (name "VDD5V") (class "Default")
      (node (ref "J3") (pin "47") (pinfunction "VCC_47") (pintype "passive"))
      (node (ref "J3") (pin "48") (pinfunction "VCC_48") (pintype "passive"))
      (node (ref "J3") (pin "49") (pinfunction "VCC_49") (pintype "passive"))
      (node (ref "J3") (pin "50") (pinfunction "VCC_50") (pintype "passive"))
      (node (ref "R19") (pin "2") (pinfunction "2_2") (pintype "passive"))
      (node (ref "R20") (pin "2") (pinfunction "2_2") (pintype "passive"))
      (node (ref "U1") (pin "7") (pinfunction "IN_7") (pintype "passive"))
    )
    (net (code "145") (name "VDD5V-LPA") (class "Default")
      (node (ref "U1") (pin "5") (pinfunction "OUTB_5") (pintype "power_in"))
    )
    (net (code "146") (name "VDD5V-LPB") (class "Default")
      (node (ref "U1") (pin "8") (pinfunction "OUTA_8") (pintype "power_in"))
    )
    (net (code "147") (name "VSS") (class "Default")
      (node (ref "C1") (pin "1") (pinfunction "1_1") (pintype "passive"))
      (node (ref "J2") (pin "6") (pinfunction "VSS_6") (pintype "power_in"))
      (node (ref "J2") (pin "9") (pinfunction "VSS_9") (pintype "power_in"))
      (node (ref "J2") (pin "A") (pinfunction "P_A") (pintype "passive"))
      (node (ref "J2") (pin "B") (pinfunction "P_B") (pintype "passive"))
      (node (ref "J2") (pin "C") (pinfunction "P_C") (pintype "passive"))
      (node (ref "J2") (pin "D") (pinfunction "P_D") (pintype "passive"))
      (node (ref "J3") (pin "1") (pinfunction "GND_1") (pintype "passive"))
      (node (ref "J3") (pin "10") (pinfunction "GND_10") (pintype "passive"))
      (node (ref "J3") (pin "11") (pinfunction "LCD-G0_11") (pintype "input"))
      (node (ref "J3") (pin "12") (pinfunction "LCD-G1_12") (pintype "input"))
      (node (ref "J3") (pin "19") (pinfunction "GND_19") (pintype "passive"))
      (node (ref "J3") (pin "2") (pinfunction "LCD-R0_2") (pintype "input"))
      (node (ref "J3") (pin "20") (pinfunction "LCD-B0_20") (pintype "input"))
      (node (ref "J3") (pin "21") (pinfunction "LCD-B1_21") (pintype "input"))
      (node (ref "J3") (pin "28") (pinfunction "GND_28") (pintype "passive"))
      (node (ref "J3") (pin "29") (pinfunction "GND_29") (pintype "passive"))
      (node (ref "J3") (pin "3") (pinfunction "LCD-R1_3") (pintype "input"))
      (node (ref "J3") (pin "31") (pinfunction "GND_31") (pintype "passive"))
      (node (ref "J3") (pin "32") (pinfunction "GND_32") (pintype "passive"))
      (node (ref "J3") (pin "36") (pinfunction "GND_36") (pintype "passive"))
      (node (ref "J3") (pin "44") (pinfunction "GND_44") (pintype "passive"))
      (node (ref "J3") (pin "46") (pinfunction "GND_46") (pintype "passive"))
      (node (ref "J3") (pin "A") (pinfunction "GND_A") (pintype "passive"))
      (node (ref "J3") (pin "B") (pinfunction "GND_B") (pintype "passive"))
      (node (ref "U1") (pin "6") (pinfunction "GND_6") (pintype "passive"))
    )
    (net (code "148") (name "unconnected-(J1A-IOA-CLKIN0p-Pad78)") (class "Default")
      (node (ref "J1") (pin "78") (pinfunction "IOA-CLKIN0p_78") (pintype "input+no_connect"))
    )
    (net (code "149") (name "unconnected-(J1A-IOA-CLKIN1n-Pad80)") (class "Default")
      (node (ref "J1") (pin "80") (pinfunction "IOA-CLKIN1n_80") (pintype "input+no_connect"))
    )
    (net (code "150") (name "unconnected-(J1A-VREF-IOA-Pad75)") (class "Default")
      (node (ref "J1") (pin "75") (pinfunction "VREF-IOA_75") (pintype "passive+no_connect"))
    )
    (net (code "151") (name "unconnected-(J1B-IOB-CLKIN0p-Pad200)") (class "Default")
      (node (ref "J1") (pin "200") (pinfunction "IOB-CLKIN0p_200") (pintype "input+no_connect"))
    )
    (net (code "152") (name "unconnected-(J1B-IOB-CLKIN1n-Pad198)") (class "Default")
      (node (ref "J1") (pin "198") (pinfunction "IOB-CLKIN1n_198") (pintype "input+no_connect"))
    )
    (net (code "153") (name "unconnected-(J1B-VREF-IOB-Pad201)") (class "Default")
      (node (ref "J1") (pin "201") (pinfunction "VREF-IOB_201") (pintype "passive+no_connect"))
    )
    (net (code "154") (name "unconnected-(J1C-IOC-CLKIN1-Pad136)") (class "Default")
      (node (ref "J1") (pin "136") (pinfunction "IOC-CLKIN1_136") (pintype "input+no_connect"))
    )
    (net (code "155") (name "unconnected-(J1C-VREF-IOC-Pad139)") (class "Default")
      (node (ref "J1") (pin "139") (pinfunction "VREF-IOC_139") (pintype "passive+no_connect"))
    )
    (net (code "156") (name "unconnected-(J1D-GPIO6-Pad31)") (class "Default")
      (node (ref "J1") (pin "31") (pinfunction "GPIO6_31") (pintype "bidirectional+no_connect"))
    )
    (net (code "157") (name "unconnected-(J1D-GPIO7-Pad33)") (class "Default")
      (node (ref "J1") (pin "33") (pinfunction "GPIO7_33") (pintype "bidirectional+no_connect"))
    )
    (net (code "158") (name "unconnected-(J1D-GPIO8-Pad35)") (class "Default")
      (node (ref "J1") (pin "35") (pinfunction "GPIO8_35") (pintype "bidirectional+no_connect"))
    )
    (net (code "159") (name "unconnected-(J1D-GPIO9-Pad37)") (class "Default")
      (node (ref "J1") (pin "37") (pinfunction "GPIO9_37") (pintype "bidirectional+no_connect"))
    )
    (net (code "160") (name "unconnected-(J1D-RGMII-RXCLK-Pad38)") (class "Default")
      (node (ref "J1") (pin "38") (pinfunction "RGMII-RXCLK_38") (pintype "input+no_connect"))
    )
    (net (code "161") (name "unconnected-(J1D-RGMII-RXCTL-Pad48)") (class "Default")
      (node (ref "J1") (pin "48") (pinfunction "RGMII-RXCTL_48") (pintype "input+no_connect"))
    )
    (net (code "162") (name "unconnected-(J1D-RGMII-RXD2-Pad42)") (class "Default")
      (node (ref "J1") (pin "42") (pinfunction "RGMII-RXD2_42") (pintype "input+no_connect"))
    )
    (net (code "163") (name "unconnected-(J1D-RGMII-RXD3-Pad40)") (class "Default")
      (node (ref "J1") (pin "40") (pinfunction "RGMII-RXD3_40") (pintype "input+no_connect"))
    )
    (net (code "164") (name "unconnected-(J1D-RGMII-TXCLK-Pad26)") (class "Default")
      (node (ref "J1") (pin "26") (pinfunction "RGMII-TXCLK_26") (pintype "output+no_connect"))
    )
    (net (code "165") (name "unconnected-(J1D-RGMII-TXD2-Pad30)") (class "Default")
      (node (ref "J1") (pin "30") (pinfunction "RGMII-TXD2_30") (pintype "output+no_connect"))
    )
    (net (code "166") (name "unconnected-(J1D-RGMII-TXD3-Pad28)") (class "Default")
      (node (ref "J1") (pin "28") (pinfunction "RGMII-TXD3_28") (pintype "output+no_connect"))
    )
  )
)
